# CM4_IO_Conn.net
KiCad netlist of a schematic drawn in Altium Designer
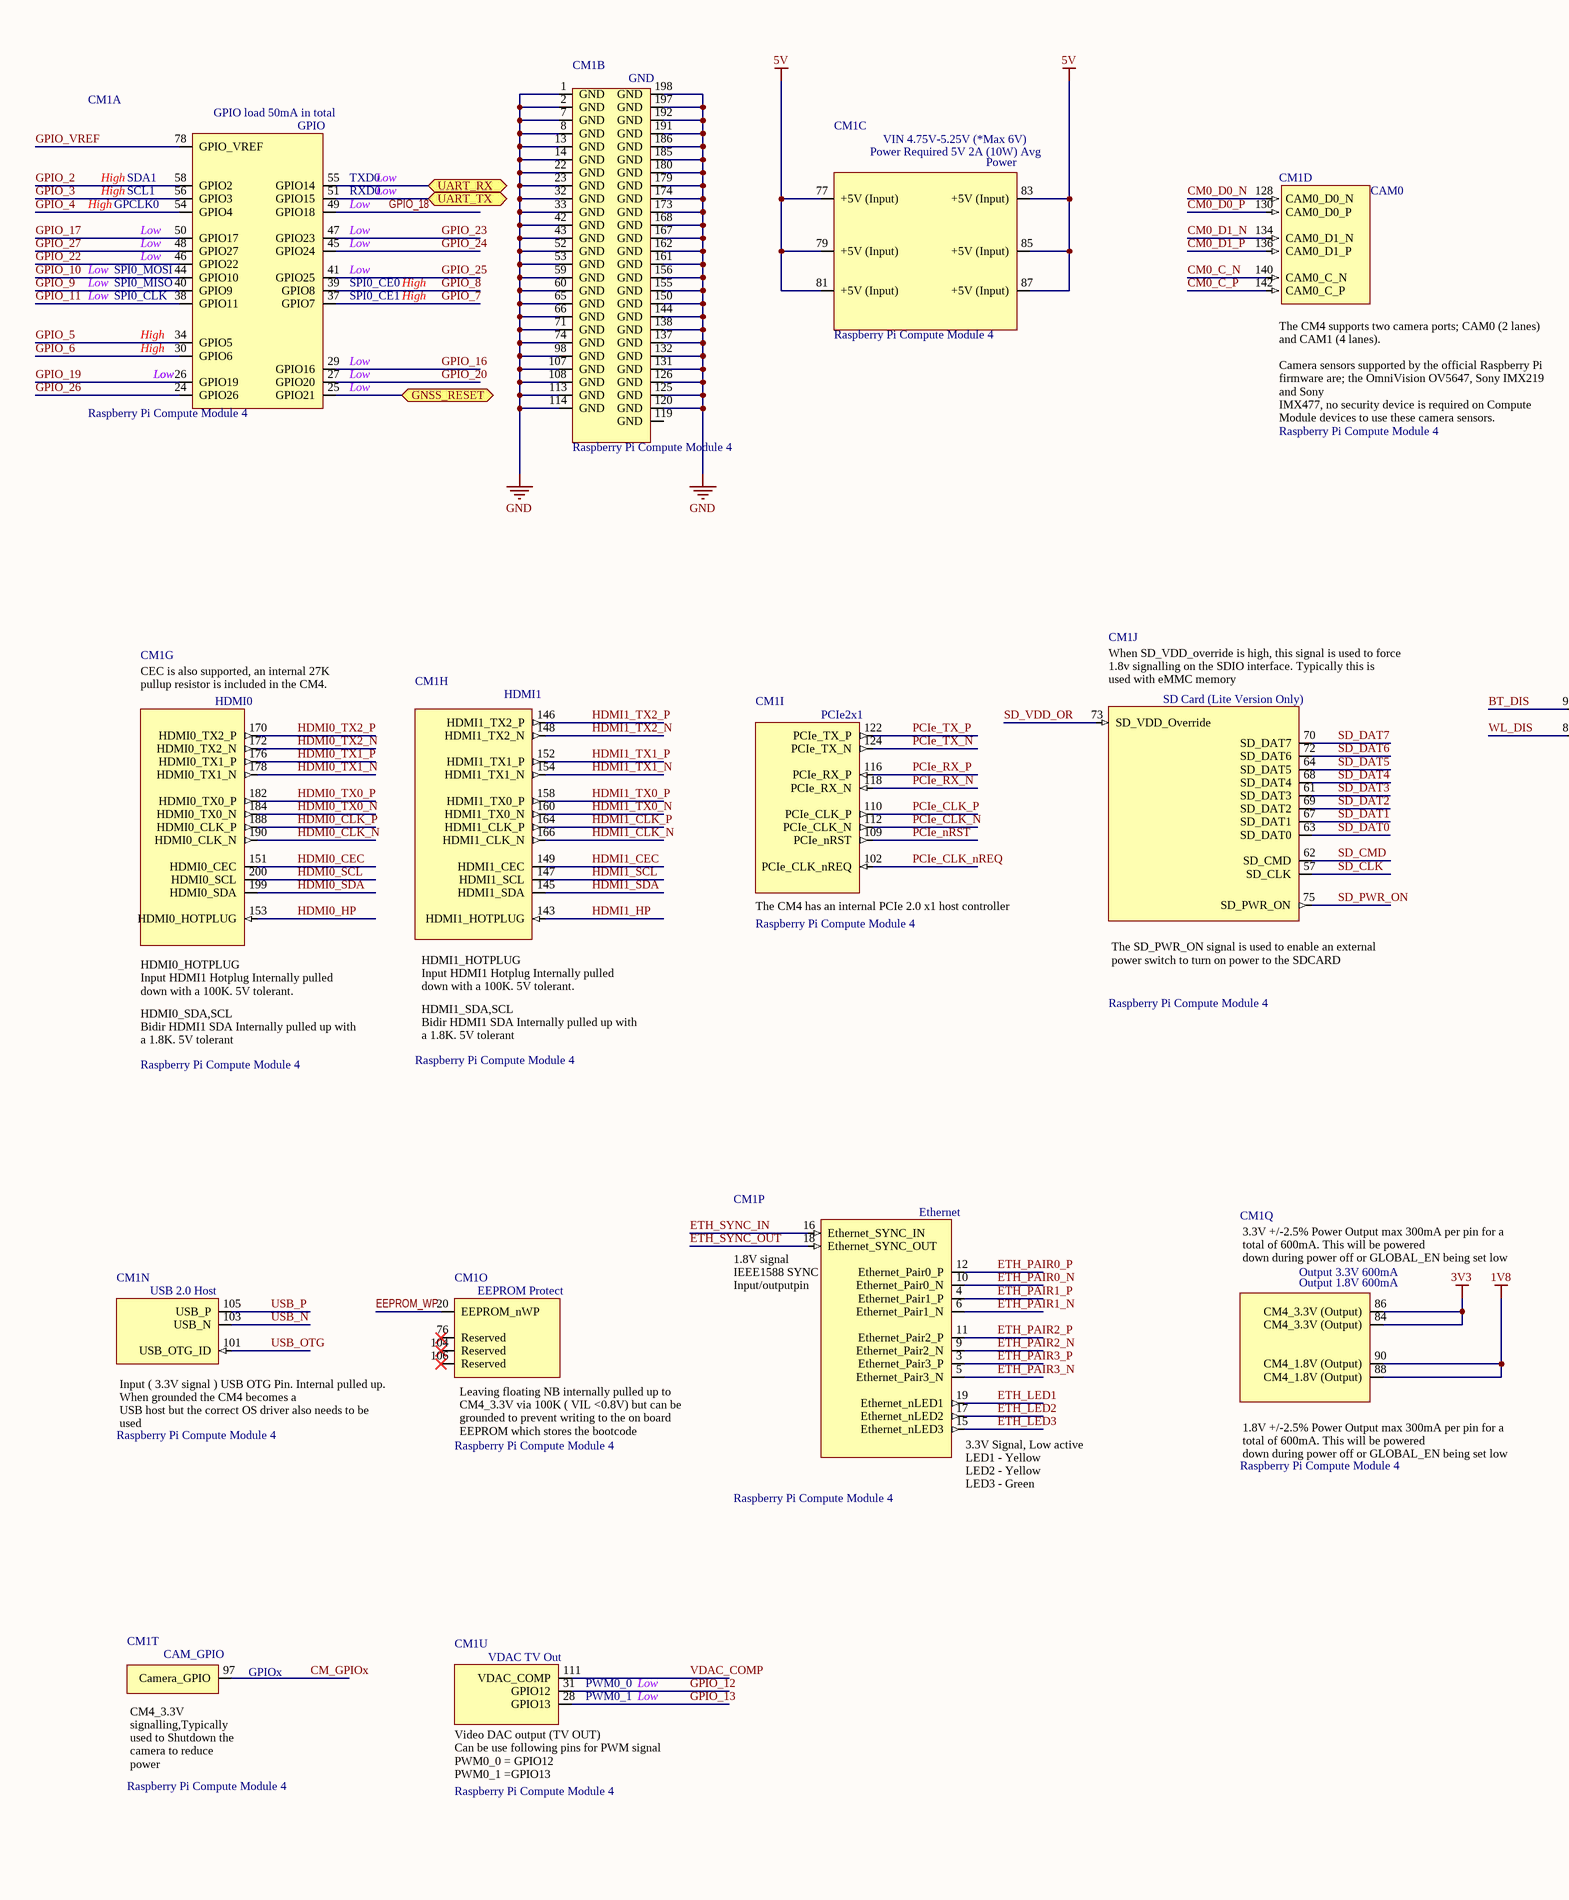
[diagram p0: CM4_IO_Conn.SchDoc, left]
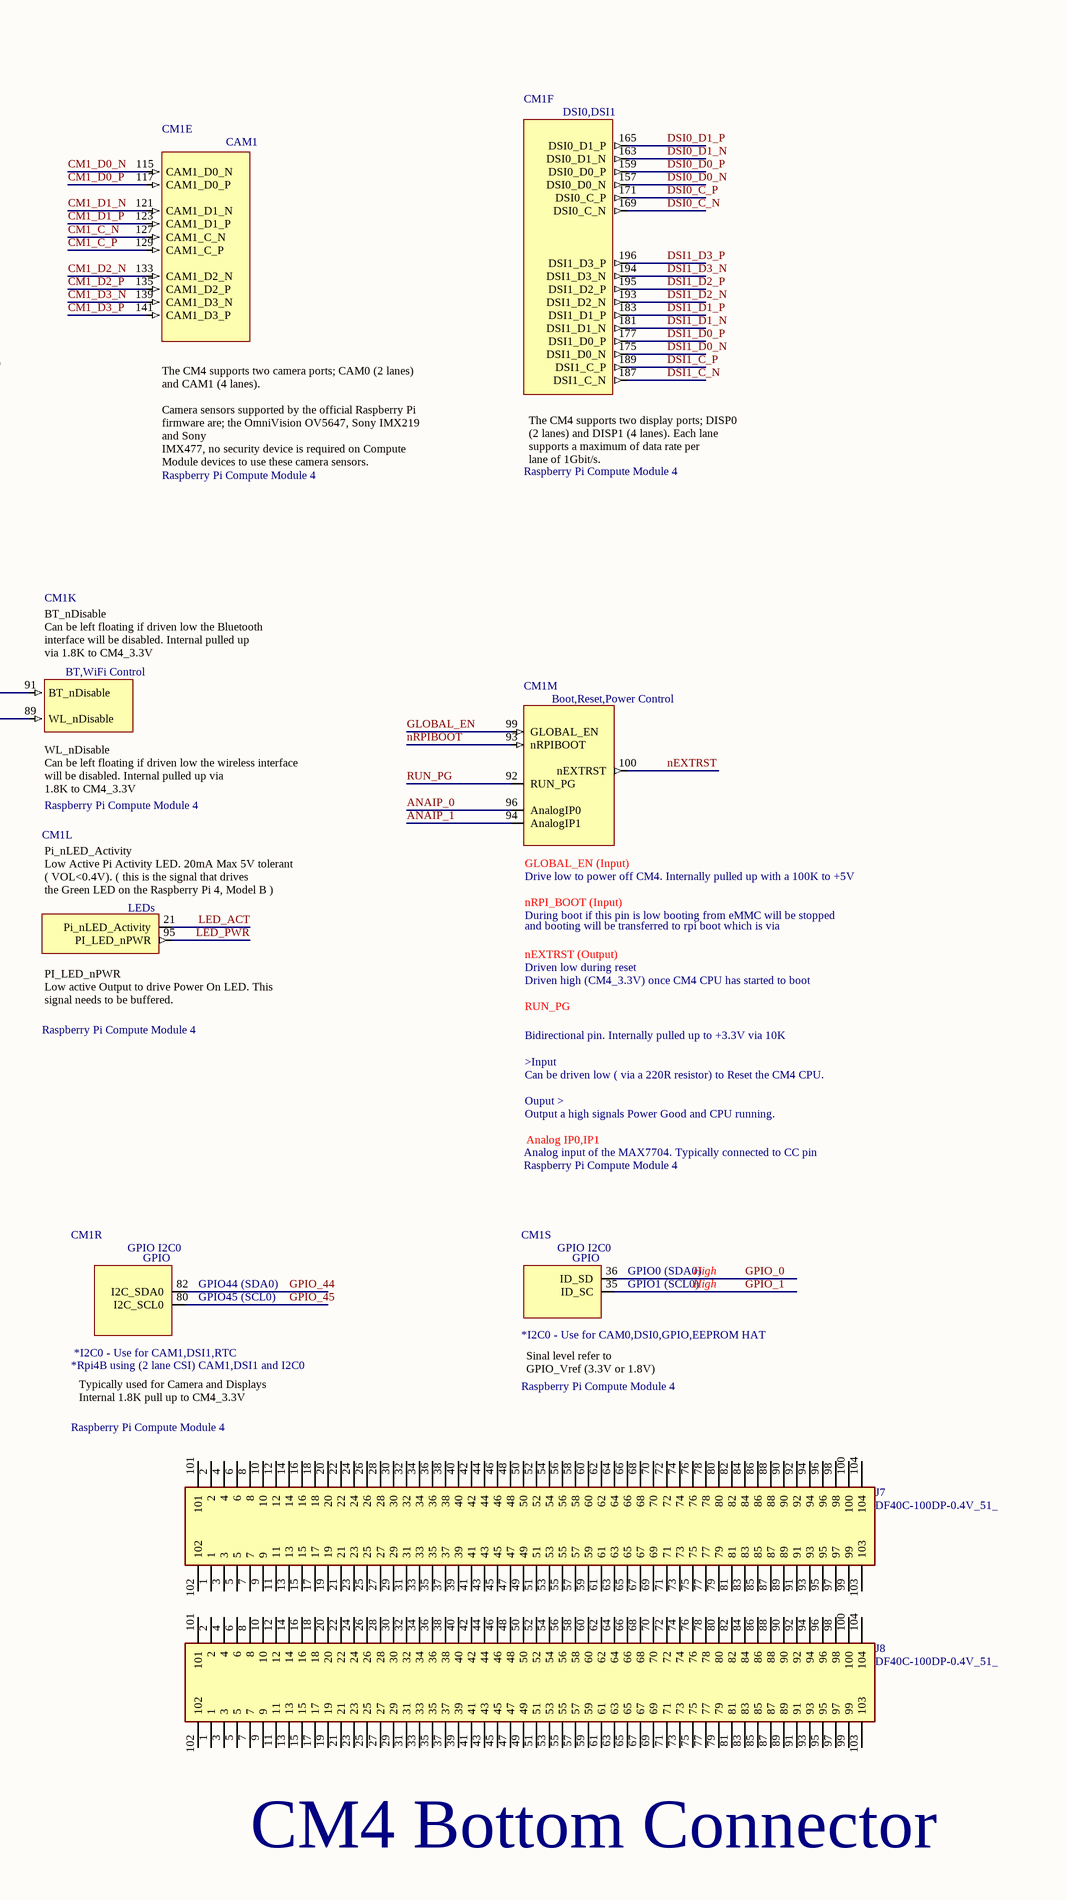
[diagram p1: CM4_IO_Conn.SchDoc, right]

(export (version "E")
  (design (tool "Eeschema 10.0.6"))
  (components
    (comp (ref "CM1")
      (value "Raspberry Pi Compute Module 4")
      (footprint "CM4-DF40HC(3.0)-100DS-0.4v_3mm_1.5mm")
      (description "Raspberry Pi Compute Module 4 by Amornthep Phunsin")
      (libsource (lib "CM4") (part "CM4"))
    )
    (comp (ref "J7")
      (value "DF40C-100DP-0.4V_51_")
      (footprint "SamacSys:DF40C100DP04V51")
      (description "Connector")
      (fields
        (field (name "MANUFACTURER_PART_NUMBER") "DF40C-100DP-0.4V(51)")
        (field (name "MOUSER PART NUMBER") "798-DF40C100DP0.4V51")
      )
      (libsource (lib "SamacSys") (part "DF40C-100DP-0.4V_51_"))
    )
    (comp (ref "J8")
      (value "DF40C-100DP-0.4V_51_")
      (footprint "SamacSys:DF40C100DP04V51")
      (description "Connector")
      (fields
        (field (name "MANUFACTURER_PART_NUMBER") "DF40C-100DP-0.4V(51)")
        (field (name "MOUSER PART NUMBER") "798-DF40C100DP0.4V51")
      )
      (libsource (lib "SamacSys") (part "DF40C-100DP-0.4V_51_"))
    )
  )
  (nets
    (net (code "1") (name "/ANAIP_0") (class "Default")
      (node (ref "CM1") (pin "96") (pinfunction "AnalogIP0_96") (pintype "passive"))
    )
    (net (code "2") (name "/ANAIP_1") (class "Default")
      (node (ref "CM1") (pin "94") (pinfunction "AnalogIP1_94") (pintype "passive"))
    )
    (net (code "3") (name "/BT_DIS") (class "Default")
      (node (ref "CM1") (pin "91") (pinfunction "BT_nDisable_91") (pintype "input"))
    )
    (net (code "4") (name "/CM0_C_N") (class "Default")
      (node (ref "CM1") (pin "140") (pinfunction "CAM0_C_N_140") (pintype "input"))
    )
    (net (code "5") (name "/CM0_C_P") (class "Default")
      (node (ref "CM1") (pin "142") (pinfunction "CAM0_C_P_142") (pintype "input"))
    )
    (net (code "6") (name "/CM0_D0_N") (class "Default")
      (node (ref "CM1") (pin "128") (pinfunction "CAM0_D0_N_128") (pintype "input"))
    )
    (net (code "7") (name "/CM0_D0_P") (class "Default")
      (node (ref "CM1") (pin "130") (pinfunction "CAM0_D0_P_130") (pintype "input"))
    )
    (net (code "8") (name "/CM0_D1_N") (class "Default")
      (node (ref "CM1") (pin "134") (pinfunction "CAM0_D1_N_134") (pintype "input"))
    )
    (net (code "9") (name "/CM0_D1_P") (class "Default")
      (node (ref "CM1") (pin "136") (pinfunction "CAM0_D1_P_136") (pintype "input"))
    )
    (net (code "10") (name "/CM1_C_N") (class "Default")
      (node (ref "CM1") (pin "127") (pinfunction "CAM1_C_N_127") (pintype "input"))
    )
    (net (code "11") (name "/CM1_C_P") (class "Default")
      (node (ref "CM1") (pin "129") (pinfunction "CAM1_C_P_129") (pintype "input"))
    )
    (net (code "12") (name "/CM1_D0_N") (class "Default")
      (node (ref "CM1") (pin "115") (pinfunction "CAM1_D0_N_115") (pintype "input"))
    )
    (net (code "13") (name "/CM1_D0_P") (class "Default")
      (node (ref "CM1") (pin "117") (pinfunction "CAM1_D0_P_117") (pintype "input"))
    )
    (net (code "14") (name "/CM1_D1_N") (class "Default")
      (node (ref "CM1") (pin "121") (pinfunction "CAM1_D1_N_121") (pintype "input"))
    )
    (net (code "15") (name "/CM1_D1_P") (class "Default")
      (node (ref "CM1") (pin "123") (pinfunction "CAM1_D1_P_123") (pintype "input"))
    )
    (net (code "16") (name "/CM1_D2_N") (class "Default")
      (node (ref "CM1") (pin "133") (pinfunction "CAM1_D2_N_133") (pintype "input"))
    )
    (net (code "17") (name "/CM1_D2_P") (class "Default")
      (node (ref "CM1") (pin "135") (pinfunction "CAM1_D2_P_135") (pintype "input"))
    )
    (net (code "18") (name "/CM1_D3_N") (class "Default")
      (node (ref "CM1") (pin "139") (pinfunction "CAM1_D3_N_139") (pintype "input"))
    )
    (net (code "19") (name "/CM1_D3_P") (class "Default")
      (node (ref "CM1") (pin "141") (pinfunction "CAM1_D3_P_141") (pintype "input"))
    )
    (net (code "20") (name "/CM_GPIOx") (class "Default")
      (node (ref "CM1") (pin "97") (pinfunction "Camera_GPIO_97") (pintype "passive"))
    )
    (net (code "21") (name "/DSI0_C_N") (class "Default")
      (node (ref "CM1") (pin "169") (pinfunction "DSI0_C_N_169") (pintype "output"))
    )
    (net (code "22") (name "/DSI0_C_P") (class "Default")
      (node (ref "CM1") (pin "171") (pinfunction "DSI0_C_P_171") (pintype "output"))
    )
    (net (code "23") (name "/DSI0_D0_N") (class "Default")
      (node (ref "CM1") (pin "157") (pinfunction "DSI0_D0_N_157") (pintype "output"))
    )
    (net (code "24") (name "/DSI0_D0_P") (class "Default")
      (node (ref "CM1") (pin "159") (pinfunction "DSI0_D0_P_159") (pintype "output"))
    )
    (net (code "25") (name "/DSI0_D1_N") (class "Default")
      (node (ref "CM1") (pin "163") (pinfunction "DSI0_D1_N_163") (pintype "output"))
    )
    (net (code "26") (name "/DSI0_D1_P") (class "Default")
      (node (ref "CM1") (pin "165") (pinfunction "DSI0_D1_P_165") (pintype "output"))
    )
    (net (code "27") (name "/DSI1_C_N") (class "Default")
      (node (ref "CM1") (pin "187") (pinfunction "DSI1_C_N_187") (pintype "output"))
    )
    (net (code "28") (name "/DSI1_C_P") (class "Default")
      (node (ref "CM1") (pin "189") (pinfunction "DSI1_C_P_189") (pintype "output"))
    )
    (net (code "29") (name "/DSI1_D0_N") (class "Default")
      (node (ref "CM1") (pin "175") (pinfunction "DSI1_D0_N_175") (pintype "output"))
    )
    (net (code "30") (name "/DSI1_D0_P") (class "Default")
      (node (ref "CM1") (pin "177") (pinfunction "DSI1_D0_P_177") (pintype "output"))
    )
    (net (code "31") (name "/DSI1_D1_N") (class "Default")
      (node (ref "CM1") (pin "181") (pinfunction "DSI1_D1_N_181") (pintype "output"))
    )
    (net (code "32") (name "/DSI1_D1_P") (class "Default")
      (node (ref "CM1") (pin "183") (pinfunction "DSI1_D1_P_183") (pintype "output"))
    )
    (net (code "33") (name "/DSI1_D2_N") (class "Default")
      (node (ref "CM1") (pin "193") (pinfunction "DSI1_D2_N_193") (pintype "output"))
    )
    (net (code "34") (name "/DSI1_D2_P") (class "Default")
      (node (ref "CM1") (pin "195") (pinfunction "DSI1_D2_P_195") (pintype "output"))
    )
    (net (code "35") (name "/DSI1_D3_N") (class "Default")
      (node (ref "CM1") (pin "194") (pinfunction "DSI1_D3_N_194") (pintype "output"))
    )
    (net (code "36") (name "/DSI1_D3_P") (class "Default")
      (node (ref "CM1") (pin "196") (pinfunction "DSI1_D3_P_196") (pintype "output"))
    )
    (net (code "37") (name "/EEPROM_WP") (class "Default")
      (node (ref "CM1") (pin "20") (pinfunction "EEPROM_nWP_20") (pintype "passive"))
    )
    (net (code "38") (name "/ETH_LED1") (class "Default")
      (node (ref "CM1") (pin "19") (pinfunction "Ethernet_nLED1_19") (pintype "output"))
    )
    (net (code "39") (name "/ETH_LED2") (class "Default")
      (node (ref "CM1") (pin "17") (pinfunction "Ethernet_nLED2_17") (pintype "output"))
    )
    (net (code "40") (name "/ETH_LED3") (class "Default")
      (node (ref "CM1") (pin "15") (pinfunction "Ethernet_nLED3_15") (pintype "output"))
    )
    (net (code "41") (name "/ETH_PAIR0_N") (class "Default")
      (node (ref "CM1") (pin "10") (pinfunction "Ethernet_Pair0_N_10") (pintype "passive"))
    )
    (net (code "42") (name "/ETH_PAIR0_P") (class "Default")
      (node (ref "CM1") (pin "12") (pinfunction "Ethernet_Pair0_P_12") (pintype "passive"))
    )
    (net (code "43") (name "/ETH_PAIR1_N") (class "Default")
      (node (ref "CM1") (pin "6") (pinfunction "Ethernet_Pair1_N_6") (pintype "passive"))
    )
    (net (code "44") (name "/ETH_PAIR1_P") (class "Default")
      (node (ref "CM1") (pin "4") (pinfunction "Ethernet_Pair1_P_4") (pintype "passive"))
    )
    (net (code "45") (name "/ETH_PAIR2_N") (class "Default")
      (node (ref "CM1") (pin "9") (pinfunction "Ethernet_Pair2_N_9") (pintype "passive"))
    )
    (net (code "46") (name "/ETH_PAIR2_P") (class "Default")
      (node (ref "CM1") (pin "11") (pinfunction "Ethernet_Pair2_P_11") (pintype "passive"))
    )
    (net (code "47") (name "/ETH_PAIR3_N") (class "Default")
      (node (ref "CM1") (pin "5") (pinfunction "Ethernet_Pair3_N_5") (pintype "passive"))
    )
    (net (code "48") (name "/ETH_PAIR3_P") (class "Default")
      (node (ref "CM1") (pin "3") (pinfunction "Ethernet_Pair3_P_3") (pintype "passive"))
    )
    (net (code "49") (name "/ETH_SYNC_IN") (class "Default")
      (node (ref "CM1") (pin "16") (pinfunction "Ethernet_SYNC_IN_16") (pintype "input"))
    )
    (net (code "50") (name "/ETH_SYNC_OUT") (class "Default")
      (node (ref "CM1") (pin "18") (pinfunction "Ethernet_SYNC_OUT_18") (pintype "input"))
    )
    (net (code "51") (name "/GLOBAL_EN") (class "Default")
      (node (ref "CM1") (pin "99") (pinfunction "GLOBAL_EN_99") (pintype "input"))
    )
    (net (code "52") (name "/GNSS_RESET") (class "Default")
      (node (ref "CM1") (pin "25") (pinfunction "GPIO21_25") (pintype "passive"))
    )
    (net (code "53") (name "/GPIO_0") (class "Default")
      (node (ref "CM1") (pin "36") (pinfunction "ID_SD_36") (pintype "passive"))
    )
    (net (code "54") (name "/GPIO_1") (class "Default")
      (node (ref "CM1") (pin "35") (pinfunction "ID_SC_35") (pintype "passive"))
    )
    (net (code "55") (name "/GPIO_2") (class "Default")
      (node (ref "CM1") (pin "58") (pinfunction "GPIO2_58") (pintype "passive"))
    )
    (net (code "56") (name "/GPIO_3") (class "Default")
      (node (ref "CM1") (pin "56") (pinfunction "GPIO3_56") (pintype "passive"))
    )
    (net (code "57") (name "/GPIO_4") (class "Default")
      (node (ref "CM1") (pin "54") (pinfunction "GPIO4_54") (pintype "passive"))
    )
    (net (code "58") (name "/GPIO_5") (class "Default")
      (node (ref "CM1") (pin "34") (pinfunction "GPIO5_34") (pintype "passive"))
    )
    (net (code "59") (name "/GPIO_6") (class "Default")
      (node (ref "CM1") (pin "30") (pinfunction "GPIO6_30") (pintype "passive"))
    )
    (net (code "60") (name "/GPIO_7") (class "Default")
      (node (ref "CM1") (pin "37") (pinfunction "GPIO7_37") (pintype "passive"))
    )
    (net (code "61") (name "/GPIO_8") (class "Default")
      (node (ref "CM1") (pin "39") (pinfunction "GPIO8_39") (pintype "passive"))
    )
    (net (code "62") (name "/GPIO_9") (class "Default")
      (node (ref "CM1") (pin "40") (pinfunction "GPIO9_40") (pintype "passive"))
    )
    (net (code "63") (name "/GPIO_10") (class "Default")
      (node (ref "CM1") (pin "44") (pinfunction "GPIO10_44") (pintype "passive"))
    )
    (net (code "64") (name "/GPIO_11") (class "Default")
      (node (ref "CM1") (pin "38") (pinfunction "GPIO11_38") (pintype "passive"))
    )
    (net (code "65") (name "/GPIO_12") (class "Default")
      (node (ref "CM1") (pin "31") (pinfunction "GPIO12_31") (pintype "passive"))
    )
    (net (code "66") (name "/GPIO_13") (class "Default")
      (node (ref "CM1") (pin "28") (pinfunction "GPIO13_28") (pintype "passive"))
    )
    (net (code "67") (name "/GPIO_16") (class "Default")
      (node (ref "CM1") (pin "29") (pinfunction "GPIO16_29") (pintype "passive"))
    )
    (net (code "68") (name "/GPIO_17") (class "Default")
      (node (ref "CM1") (pin "50") (pinfunction "GPIO17_50") (pintype "passive"))
    )
    (net (code "69") (name "/GPIO_18") (class "Default")
      (node (ref "CM1") (pin "49") (pinfunction "GPIO18_49") (pintype "passive"))
    )
    (net (code "70") (name "/GPIO_19") (class "Default")
      (node (ref "CM1") (pin "26") (pinfunction "GPIO19_26") (pintype "passive"))
    )
    (net (code "71") (name "/GPIO_20") (class "Default")
      (node (ref "CM1") (pin "27") (pinfunction "GPIO20_27") (pintype "passive"))
    )
    (net (code "72") (name "/GPIO_22") (class "Default")
      (node (ref "CM1") (pin "46") (pinfunction "GPIO22_46") (pintype "passive"))
    )
    (net (code "73") (name "/GPIO_23") (class "Default")
      (node (ref "CM1") (pin "47") (pinfunction "GPIO23_47") (pintype "passive"))
    )
    (net (code "74") (name "/GPIO_24") (class "Default")
      (node (ref "CM1") (pin "45") (pinfunction "GPIO24_45") (pintype "passive"))
    )
    (net (code "75") (name "/GPIO_25") (class "Default")
      (node (ref "CM1") (pin "41") (pinfunction "GPIO25_41") (pintype "passive"))
    )
    (net (code "76") (name "/GPIO_26") (class "Default")
      (node (ref "CM1") (pin "24") (pinfunction "GPIO26_24") (pintype "passive"))
    )
    (net (code "77") (name "/GPIO_27") (class "Default")
      (node (ref "CM1") (pin "48") (pinfunction "GPIO27_48") (pintype "passive"))
    )
    (net (code "78") (name "/GPIO_44") (class "Default")
      (node (ref "CM1") (pin "82") (pinfunction "I2C_SDA0_82") (pintype "passive"))
    )
    (net (code "79") (name "/GPIO_45") (class "Default")
      (node (ref "CM1") (pin "80") (pinfunction "I2C_SCL0_80") (pintype "passive"))
    )
    (net (code "80") (name "/GPIO_VREF") (class "Default")
      (node (ref "CM1") (pin "78") (pinfunction "GPIO_VREF_78") (pintype "power_in"))
    )
    (net (code "81") (name "/HDMI0_CEC") (class "Default")
      (node (ref "CM1") (pin "151") (pinfunction "HDMI0_CEC_151") (pintype "open_collector"))
    )
    (net (code "82") (name "/HDMI0_CLK_N") (class "Default")
      (node (ref "CM1") (pin "190") (pinfunction "HDMI0_CLK_N_190") (pintype "output"))
    )
    (net (code "83") (name "/HDMI0_CLK_P") (class "Default")
      (node (ref "CM1") (pin "188") (pinfunction "HDMI0_CLK_P_188") (pintype "output"))
    )
    (net (code "84") (name "/HDMI0_HP") (class "Default")
      (node (ref "CM1") (pin "153") (pinfunction "HDMI0_HOTPLUG_153") (pintype "input"))
    )
    (net (code "85") (name "/HDMI0_SCL") (class "Default")
      (node (ref "CM1") (pin "200") (pinfunction "HDMI0_SCL_200") (pintype "open_collector"))
    )
    (net (code "86") (name "/HDMI0_SDA") (class "Default")
      (node (ref "CM1") (pin "199") (pinfunction "HDMI0_SDA_199") (pintype "bidirectional"))
    )
    (net (code "87") (name "/HDMI0_TX0_N") (class "Default")
      (node (ref "CM1") (pin "184") (pinfunction "HDMI0_TX0_N_184") (pintype "output"))
    )
    (net (code "88") (name "/HDMI0_TX0_P") (class "Default")
      (node (ref "CM1") (pin "182") (pinfunction "HDMI0_TX0_P_182") (pintype "output"))
    )
    (net (code "89") (name "/HDMI0_TX1_N") (class "Default")
      (node (ref "CM1") (pin "178") (pinfunction "HDMI0_TX1_N_178") (pintype "output"))
    )
    (net (code "90") (name "/HDMI0_TX1_P") (class "Default")
      (node (ref "CM1") (pin "176") (pinfunction "HDMI0_TX1_P_176") (pintype "output"))
    )
    (net (code "91") (name "/HDMI0_TX2_N") (class "Default")
      (node (ref "CM1") (pin "172") (pinfunction "HDMI0_TX2_N_172") (pintype "output"))
    )
    (net (code "92") (name "/HDMI0_TX2_P") (class "Default")
      (node (ref "CM1") (pin "170") (pinfunction "HDMI0_TX2_P_170") (pintype "output"))
    )
    (net (code "93") (name "/HDMI1_CEC") (class "Default")
      (node (ref "CM1") (pin "149") (pinfunction "HDMI1_CEC_149") (pintype "open_collector"))
    )
    (net (code "94") (name "/HDMI1_CLK_N") (class "Default")
      (node (ref "CM1") (pin "166") (pinfunction "HDMI1_CLK_N_166") (pintype "output"))
    )
    (net (code "95") (name "/HDMI1_CLK_P") (class "Default")
      (node (ref "CM1") (pin "164") (pinfunction "HDMI1_CLK_P_164") (pintype "output"))
    )
    (net (code "96") (name "/HDMI1_HP") (class "Default")
      (node (ref "CM1") (pin "143") (pinfunction "HDMI1_HOTPLUG_143") (pintype "input"))
    )
    (net (code "97") (name "/HDMI1_SCL") (class "Default")
      (node (ref "CM1") (pin "147") (pinfunction "HDMI1_SCL_147") (pintype "open_collector"))
    )
    (net (code "98") (name "/HDMI1_SDA") (class "Default")
      (node (ref "CM1") (pin "145") (pinfunction "HDMI1_SDA_145") (pintype "bidirectional"))
    )
    (net (code "99") (name "/HDMI1_TX0_N") (class "Default")
      (node (ref "CM1") (pin "160") (pinfunction "HDMI1_TX0_N_160") (pintype "output"))
    )
    (net (code "100") (name "/HDMI1_TX0_P") (class "Default")
      (node (ref "CM1") (pin "158") (pinfunction "HDMI1_TX0_P_158") (pintype "output"))
    )
    (net (code "101") (name "/HDMI1_TX1_N") (class "Default")
      (node (ref "CM1") (pin "154") (pinfunction "HDMI1_TX1_N_154") (pintype "output"))
    )
    (net (code "102") (name "/HDMI1_TX1_P") (class "Default")
      (node (ref "CM1") (pin "152") (pinfunction "HDMI1_TX1_P_152") (pintype "output"))
    )
    (net (code "103") (name "/HDMI1_TX2_N") (class "Default")
      (node (ref "CM1") (pin "148") (pinfunction "HDMI1_TX2_N_148") (pintype "output"))
    )
    (net (code "104") (name "/HDMI1_TX2_P") (class "Default")
      (node (ref "CM1") (pin "146") (pinfunction "HDMI1_TX2_P_146") (pintype "output"))
    )
    (net (code "105") (name "/LED_ACT") (class "Default")
      (node (ref "CM1") (pin "21") (pinfunction "Pi_nLED_Activity_21") (pintype "open_collector"))
    )
    (net (code "106") (name "/LED_PWR") (class "Default")
      (node (ref "CM1") (pin "95") (pinfunction "PI_LED_nPWR_95") (pintype "output"))
    )
    (net (code "107") (name "/PCIe_CLK_N") (class "Default")
      (node (ref "CM1") (pin "112") (pinfunction "PCIe_CLK_N_112") (pintype "output"))
    )
    (net (code "108") (name "/PCIe_CLK_P") (class "Default")
      (node (ref "CM1") (pin "110") (pinfunction "PCIe_CLK_P_110") (pintype "output"))
    )
    (net (code "109") (name "/PCIe_CLK_nREQ") (class "Default")
      (node (ref "CM1") (pin "102") (pinfunction "PCIe_CLK_nREQ_102") (pintype "input"))
    )
    (net (code "110") (name "/PCIe_RX_N") (class "Default")
      (node (ref "CM1") (pin "118") (pinfunction "PCIe_RX_N_118") (pintype "input"))
    )
    (net (code "111") (name "/PCIe_RX_P") (class "Default")
      (node (ref "CM1") (pin "116") (pinfunction "PCIe_RX_P_116") (pintype "input"))
    )
    (net (code "112") (name "/PCIe_TX_N") (class "Default")
      (node (ref "CM1") (pin "124") (pinfunction "PCIe_TX_N_124") (pintype "output"))
    )
    (net (code "113") (name "/PCIe_TX_P") (class "Default")
      (node (ref "CM1") (pin "122") (pinfunction "PCIe_TX_P_122") (pintype "output"))
    )
    (net (code "114") (name "/PCIe_nRST") (class "Default")
      (node (ref "CM1") (pin "109") (pinfunction "PCIe_nRST_109") (pintype "output"))
    )
    (net (code "115") (name "/RUN_PG") (class "Default")
      (node (ref "CM1") (pin "92") (pinfunction "RUN_PG_92") (pintype "passive"))
    )
    (net (code "116") (name "/SD_CLK") (class "Default")
      (node (ref "CM1") (pin "57") (pinfunction "SD_CLK_57") (pintype "passive"))
    )
    (net (code "117") (name "/SD_CMD") (class "Default")
      (node (ref "CM1") (pin "62") (pinfunction "SD_CMD_62") (pintype "passive"))
    )
    (net (code "118") (name "/SD_DAT0") (class "Default")
      (node (ref "CM1") (pin "63") (pinfunction "SD_DAT0_63") (pintype "passive"))
    )
    (net (code "119") (name "/SD_DAT1") (class "Default")
      (node (ref "CM1") (pin "67") (pinfunction "SD_DAT1_67") (pintype "passive"))
    )
    (net (code "120") (name "/SD_DAT2") (class "Default")
      (node (ref "CM1") (pin "69") (pinfunction "SD_DAT2_69") (pintype "passive"))
    )
    (net (code "121") (name "/SD_DAT3") (class "Default")
      (node (ref "CM1") (pin "61") (pinfunction "SD_DAT3_61") (pintype "passive"))
    )
    (net (code "122") (name "/SD_DAT4") (class "Default")
      (node (ref "CM1") (pin "68") (pinfunction "SD_DAT4_68") (pintype "passive"))
    )
    (net (code "123") (name "/SD_DAT5") (class "Default")
      (node (ref "CM1") (pin "64") (pinfunction "SD_DAT5_64") (pintype "passive"))
    )
    (net (code "124") (name "/SD_DAT6") (class "Default")
      (node (ref "CM1") (pin "72") (pinfunction "SD_DAT6_72") (pintype "passive"))
    )
    (net (code "125") (name "/SD_DAT7") (class "Default")
      (node (ref "CM1") (pin "70") (pinfunction "SD_DAT7_70") (pintype "passive"))
    )
    (net (code "126") (name "/SD_PWR_ON") (class "Default")
      (node (ref "CM1") (pin "75") (pinfunction "SD_PWR_ON_75") (pintype "output"))
    )
    (net (code "127") (name "/SD_VDD_OR") (class "Default")
      (node (ref "CM1") (pin "73") (pinfunction "SD_VDD_Override_73") (pintype "input"))
    )
    (net (code "128") (name "/UART_RX") (class "Default")
      (node (ref "CM1") (pin "55") (pinfunction "GPIO14_55") (pintype "passive"))
    )
    (net (code "129") (name "/UART_TX") (class "Default")
      (node (ref "CM1") (pin "51") (pinfunction "GPIO15_51") (pintype "passive"))
    )
    (net (code "130") (name "/USB_N") (class "Default")
      (node (ref "CM1") (pin "103") (pinfunction "USB_N_103") (pintype "passive"))
    )
    (net (code "131") (name "/USB_OTG") (class "Default")
      (node (ref "CM1") (pin "101") (pinfunction "USB_OTG_ID_101") (pintype "input"))
    )
    (net (code "132") (name "/USB_P") (class "Default")
      (node (ref "CM1") (pin "105") (pinfunction "USB_P_105") (pintype "passive"))
    )
    (net (code "133") (name "/VDAC_COMP") (class "Default")
      (node (ref "CM1") (pin "111") (pinfunction "VDAC_COMP_111") (pintype "passive"))
    )
    (net (code "134") (name "/WL_DIS") (class "Default")
      (node (ref "CM1") (pin "89") (pinfunction "WL_nDisable_89") (pintype "input"))
    )
    (net (code "135") (name "/nEXTRST") (class "Default")
      (node (ref "CM1") (pin "100") (pinfunction "nEXTRST_100") (pintype "output"))
    )
    (net (code "136") (name "/nRPIBOOT") (class "Default")
      (node (ref "CM1") (pin "93") (pinfunction "nRPIBOOT_93") (pintype "input"))
    )
    (net (code "137") (name "1V8") (class "Default")
      (node (ref "CM1") (pin "88") (pinfunction "CM4_1.8V_(Output)_88") (pintype "power_in"))
      (node (ref "CM1") (pin "90") (pinfunction "CM4_1.8V_(Output)_90") (pintype "power_in"))
    )
    (net (code "138") (name "3V3") (class "Default")
      (node (ref "CM1") (pin "84") (pinfunction "CM4_3.3V_(Output)_84") (pintype "power_in"))
      (node (ref "CM1") (pin "86") (pinfunction "CM4_3.3V_(Output)_86") (pintype "power_in"))
    )
    (net (code "139") (name "5V") (class "Default")
      (node (ref "CM1") (pin "77") (pinfunction "+5V_(Input)_77") (pintype "power_in"))
      (node (ref "CM1") (pin "79") (pinfunction "+5V_(Input)_79") (pintype "power_in"))
      (node (ref "CM1") (pin "81") (pinfunction "+5V_(Input)_81") (pintype "power_in"))
      (node (ref "CM1") (pin "83") (pinfunction "+5V_(Input)_83") (pintype "power_in"))
      (node (ref "CM1") (pin "85") (pinfunction "+5V_(Input)_85") (pintype "power_in"))
      (node (ref "CM1") (pin "87") (pinfunction "+5V_(Input)_87") (pintype "power_in"))
    )
    (net (code "140") (name "GND") (class "Default")
      (node (ref "CM1") (pin "1") (pinfunction "GND_1") (pintype "power_in"))
      (node (ref "CM1") (pin "107") (pinfunction "GND_107") (pintype "power_in"))
      (node (ref "CM1") (pin "108") (pinfunction "GND_108") (pintype "power_in"))
      (node (ref "CM1") (pin "113") (pinfunction "GND_113") (pintype "power_in"))
      (node (ref "CM1") (pin "114") (pinfunction "GND_114") (pintype "power_in"))
      (node (ref "CM1") (pin "120") (pinfunction "GND_120") (pintype "power_in"))
      (node (ref "CM1") (pin "125") (pinfunction "GND_125") (pintype "power_in"))
      (node (ref "CM1") (pin "126") (pinfunction "GND_126") (pintype "power_in"))
      (node (ref "CM1") (pin "13") (pinfunction "GND_13") (pintype "power_in"))
      (node (ref "CM1") (pin "131") (pinfunction "GND_131") (pintype "power_in"))
      (node (ref "CM1") (pin "132") (pinfunction "GND_132") (pintype "power_in"))
      (node (ref "CM1") (pin "137") (pinfunction "GND_137") (pintype "power_in"))
      (node (ref "CM1") (pin "138") (pinfunction "GND_138") (pintype "power_in"))
      (node (ref "CM1") (pin "14") (pinfunction "GND_14") (pintype "power_in"))
      (node (ref "CM1") (pin "144") (pinfunction "GND_144") (pintype "power_in"))
      (node (ref "CM1") (pin "150") (pinfunction "GND_150") (pintype "power_in"))
      (node (ref "CM1") (pin "155") (pinfunction "GND_155") (pintype "power_in"))
      (node (ref "CM1") (pin "156") (pinfunction "GND_156") (pintype "power_in"))
      (node (ref "CM1") (pin "161") (pinfunction "GND_161") (pintype "power_in"))
      (node (ref "CM1") (pin "162") (pinfunction "GND_162") (pintype "power_in"))
      (node (ref "CM1") (pin "167") (pinfunction "GND_167") (pintype "power_in"))
      (node (ref "CM1") (pin "168") (pinfunction "GND_168") (pintype "power_in"))
      (node (ref "CM1") (pin "173") (pinfunction "GND_173") (pintype "power_in"))
      (node (ref "CM1") (pin "174") (pinfunction "GND_174") (pintype "power_in"))
      (node (ref "CM1") (pin "179") (pinfunction "GND_179") (pintype "power_in"))
      (node (ref "CM1") (pin "180") (pinfunction "GND_180") (pintype "power_in"))
      (node (ref "CM1") (pin "185") (pinfunction "GND_185") (pintype "power_in"))
      (node (ref "CM1") (pin "186") (pinfunction "GND_186") (pintype "power_in"))
      (node (ref "CM1") (pin "191") (pinfunction "GND_191") (pintype "power_in"))
      (node (ref "CM1") (pin "192") (pinfunction "GND_192") (pintype "power_in"))
      (node (ref "CM1") (pin "197") (pinfunction "GND_197") (pintype "power_in"))
      (node (ref "CM1") (pin "198") (pinfunction "GND_198") (pintype "power_in"))
      (node (ref "CM1") (pin "2") (pinfunction "GND_2") (pintype "power_in"))
      (node (ref "CM1") (pin "22") (pinfunction "GND_22") (pintype "power_in"))
      (node (ref "CM1") (pin "23") (pinfunction "GND_23") (pintype "power_in"))
      (node (ref "CM1") (pin "32") (pinfunction "GND_32") (pintype "power_in"))
      (node (ref "CM1") (pin "33") (pinfunction "GND_33") (pintype "power_in"))
      (node (ref "CM1") (pin "42") (pinfunction "GND_42") (pintype "power_in"))
      (node (ref "CM1") (pin "43") (pinfunction "GND_43") (pintype "power_in"))
      (node (ref "CM1") (pin "52") (pinfunction "GND_52") (pintype "power_in"))
      (node (ref "CM1") (pin "53") (pinfunction "GND_53") (pintype "power_in"))
      (node (ref "CM1") (pin "59") (pinfunction "GND_59") (pintype "power_in"))
      (node (ref "CM1") (pin "60") (pinfunction "GND_60") (pintype "power_in"))
      (node (ref "CM1") (pin "65") (pinfunction "GND_65") (pintype "power_in"))
      (node (ref "CM1") (pin "66") (pinfunction "GND_66") (pintype "power_in"))
      (node (ref "CM1") (pin "7") (pinfunction "GND_7") (pintype "power_in"))
      (node (ref "CM1") (pin "71") (pinfunction "GND_71") (pintype "power_in"))
      (node (ref "CM1") (pin "74") (pinfunction "GND_74") (pintype "power_in"))
      (node (ref "CM1") (pin "8") (pinfunction "GND_8") (pintype "power_in"))
      (node (ref "CM1") (pin "98") (pinfunction "GND_98") (pintype "power_in"))
    )
    (net (code "141") (name "unconnected-(CM1B-GND-Pad119)") (class "Default")
      (node (ref "CM1") (pin "119") (pinfunction "GND_119") (pintype "power_in"))
    )
    (net (code "142") (name "unconnected-(CM1O-Reserved-Pad76)") (class "Default")
      (node (ref "CM1") (pin "76") (pinfunction "Reserved_76") (pintype "passive+no_connect"))
    )
    (net (code "143") (name "unconnected-(CM1O-Reserved-Pad104)") (class "Default")
      (node (ref "CM1") (pin "104") (pinfunction "Reserved_104") (pintype "passive+no_connect"))
    )
    (net (code "144") (name "unconnected-(CM1O-Reserved-Pad106)") (class "Default")
      (node (ref "CM1") (pin "106") (pinfunction "Reserved_106") (pintype "passive+no_connect"))
    )
    (net (code "145") (name "unconnected-(J7-Pad1)") (class "Default")
      (node (ref "J7") (pin "1") (pinfunction "1_1") (pintype "passive"))
    )
    (net (code "146") (name "unconnected-(J7-Pad2)") (class "Default")
      (node (ref "J7") (pin "2") (pinfunction "2_2") (pintype "passive"))
    )
    (net (code "147") (name "unconnected-(J7-Pad3)") (class "Default")
      (node (ref "J7") (pin "3") (pinfunction "3_3") (pintype "passive"))
    )
    (net (code "148") (name "unconnected-(J7-Pad4)") (class "Default")
      (node (ref "J7") (pin "4") (pinfunction "4_4") (pintype "passive"))
    )
    (net (code "149") (name "unconnected-(J7-Pad5)") (class "Default")
      (node (ref "J7") (pin "5") (pinfunction "5_5") (pintype "passive"))
    )
    (net (code "150") (name "unconnected-(J7-Pad6)") (class "Default")
      (node (ref "J7") (pin "6") (pinfunction "6_6") (pintype "passive"))
    )
    (net (code "151") (name "unconnected-(J7-Pad7)") (class "Default")
      (node (ref "J7") (pin "7") (pinfunction "7_7") (pintype "passive"))
    )
    (net (code "152") (name "unconnected-(J7-Pad8)") (class "Default")
      (node (ref "J7") (pin "8") (pinfunction "8_8") (pintype "passive"))
    )
    (net (code "153") (name "unconnected-(J7-Pad9)") (class "Default")
      (node (ref "J7") (pin "9") (pinfunction "9_9") (pintype "passive"))
    )
    (net (code "154") (name "unconnected-(J7-Pad10)") (class "Default")
      (node (ref "J7") (pin "10") (pinfunction "10_10") (pintype "passive"))
    )
    (net (code "155") (name "unconnected-(J7-Pad11)") (class "Default")
      (node (ref "J7") (pin "11") (pinfunction "11_11") (pintype "passive"))
    )
    (net (code "156") (name "unconnected-(J7-Pad12)") (class "Default")
      (node (ref "J7") (pin "12") (pinfunction "12_12") (pintype "passive"))
    )
    (net (code "157") (name "unconnected-(J7-Pad13)") (class "Default")
      (node (ref "J7") (pin "13") (pinfunction "13_13") (pintype "passive"))
    )
    (net (code "158") (name "unconnected-(J7-Pad14)") (class "Default")
      (node (ref "J7") (pin "14") (pinfunction "14_14") (pintype "passive"))
    )
    (net (code "159") (name "unconnected-(J7-Pad15)") (class "Default")
      (node (ref "J7") (pin "15") (pinfunction "15_15") (pintype "passive"))
    )
    (net (code "160") (name "unconnected-(J7-Pad16)") (class "Default")
      (node (ref "J7") (pin "16") (pinfunction "16_16") (pintype "passive"))
    )
    (net (code "161") (name "unconnected-(J7-Pad17)") (class "Default")
      (node (ref "J7") (pin "17") (pinfunction "17_17") (pintype "passive"))
    )
    (net (code "162") (name "unconnected-(J7-Pad18)") (class "Default")
      (node (ref "J7") (pin "18") (pinfunction "18_18") (pintype "passive"))
    )
    (net (code "163") (name "unconnected-(J7-Pad19)") (class "Default")
      (node (ref "J7") (pin "19") (pinfunction "19_19") (pintype "passive"))
    )
    (net (code "164") (name "unconnected-(J7-Pad20)") (class "Default")
      (node (ref "J7") (pin "20") (pinfunction "20_20") (pintype "passive"))
    )
    (net (code "165") (name "unconnected-(J7-Pad21)") (class "Default")
      (node (ref "J7") (pin "21") (pinfunction "21_21") (pintype "passive"))
    )
    (net (code "166") (name "unconnected-(J7-Pad22)") (class "Default")
      (node (ref "J7") (pin "22") (pinfunction "22_22") (pintype "passive"))
    )
    (net (code "167") (name "unconnected-(J7-Pad23)") (class "Default")
      (node (ref "J7") (pin "23") (pinfunction "23_23") (pintype "passive"))
    )
    (net (code "168") (name "unconnected-(J7-Pad24)") (class "Default")
      (node (ref "J7") (pin "24") (pinfunction "24_24") (pintype "passive"))
    )
    (net (code "169") (name "unconnected-(J7-Pad25)") (class "Default")
      (node (ref "J7") (pin "25") (pinfunction "25_25") (pintype "passive"))
    )
    (net (code "170") (name "unconnected-(J7-Pad26)") (class "Default")
      (node (ref "J7") (pin "26") (pinfunction "26_26") (pintype "passive"))
    )
    (net (code "171") (name "unconnected-(J7-Pad27)") (class "Default")
      (node (ref "J7") (pin "27") (pinfunction "27_27") (pintype "passive"))
    )
    (net (code "172") (name "unconnected-(J7-Pad28)") (class "Default")
      (node (ref "J7") (pin "28") (pinfunction "28_28") (pintype "passive"))
    )
    (net (code "173") (name "unconnected-(J7-Pad29)") (class "Default")
      (node (ref "J7") (pin "29") (pinfunction "29_29") (pintype "passive"))
    )
    (net (code "174") (name "unconnected-(J7-Pad30)") (class "Default")
      (node (ref "J7") (pin "30") (pinfunction "30_30") (pintype "passive"))
    )
    (net (code "175") (name "unconnected-(J7-Pad31)") (class "Default")
      (node (ref "J7") (pin "31") (pinfunction "31_31") (pintype "passive"))
    )
    (net (code "176") (name "unconnected-(J7-Pad32)") (class "Default")
      (node (ref "J7") (pin "32") (pinfunction "32_32") (pintype "passive"))
    )
    (net (code "177") (name "unconnected-(J7-Pad33)") (class "Default")
      (node (ref "J7") (pin "33") (pinfunction "33_33") (pintype "passive"))
    )
    (net (code "178") (name "unconnected-(J7-Pad34)") (class "Default")
      (node (ref "J7") (pin "34") (pinfunction "34_34") (pintype "passive"))
    )
    (net (code "179") (name "unconnected-(J7-Pad35)") (class "Default")
      (node (ref "J7") (pin "35") (pinfunction "35_35") (pintype "passive"))
    )
    (net (code "180") (name "unconnected-(J7-Pad36)") (class "Default")
      (node (ref "J7") (pin "36") (pinfunction "36_36") (pintype "passive"))
    )
    (net (code "181") (name "unconnected-(J7-Pad37)") (class "Default")
      (node (ref "J7") (pin "37") (pinfunction "37_37") (pintype "passive"))
    )
    (net (code "182") (name "unconnected-(J7-Pad38)") (class "Default")
      (node (ref "J7") (pin "38") (pinfunction "38_38") (pintype "passive"))
    )
    (net (code "183") (name "unconnected-(J7-Pad39)") (class "Default")
      (node (ref "J7") (pin "39") (pinfunction "39_39") (pintype "passive"))
    )
    (net (code "184") (name "unconnected-(J7-Pad40)") (class "Default")
      (node (ref "J7") (pin "40") (pinfunction "40_40") (pintype "passive"))
    )
    (net (code "185") (name "unconnected-(J7-Pad41)") (class "Default")
      (node (ref "J7") (pin "41") (pinfunction "41_41") (pintype "passive"))
    )
    (net (code "186") (name "unconnected-(J7-Pad42)") (class "Default")
      (node (ref "J7") (pin "42") (pinfunction "42_42") (pintype "passive"))
    )
    (net (code "187") (name "unconnected-(J7-Pad43)") (class "Default")
      (node (ref "J7") (pin "43") (pinfunction "43_43") (pintype "passive"))
    )
    (net (code "188") (name "unconnected-(J7-Pad44)") (class "Default")
      (node (ref "J7") (pin "44") (pinfunction "44_44") (pintype "passive"))
    )
    (net (code "189") (name "unconnected-(J7-Pad45)") (class "Default")
      (node (ref "J7") (pin "45") (pinfunction "45_45") (pintype "passive"))
    )
    (net (code "190") (name "unconnected-(J7-Pad46)") (class "Default")
      (node (ref "J7") (pin "46") (pinfunction "46_46") (pintype "passive"))
    )
    (net (code "191") (name "unconnected-(J7-Pad47)") (class "Default")
      (node (ref "J7") (pin "47") (pinfunction "47_47") (pintype "passive"))
    )
    (net (code "192") (name "unconnected-(J7-Pad48)") (class "Default")
      (node (ref "J7") (pin "48") (pinfunction "48_48") (pintype "passive"))
    )
    (net (code "193") (name "unconnected-(J7-Pad49)") (class "Default")
      (node (ref "J7") (pin "49") (pinfunction "49_49") (pintype "passive"))
    )
    (net (code "194") (name "unconnected-(J7-Pad50)") (class "Default")
      (node (ref "J7") (pin "50") (pinfunction "50_50") (pintype "passive"))
    )
    (net (code "195") (name "unconnected-(J7-Pad51)") (class "Default")
      (node (ref "J7") (pin "51") (pinfunction "51_51") (pintype "passive"))
    )
    (net (code "196") (name "unconnected-(J7-Pad52)") (class "Default")
      (node (ref "J7") (pin "52") (pinfunction "52_52") (pintype "passive"))
    )
    (net (code "197") (name "unconnected-(J7-Pad53)") (class "Default")
      (node (ref "J7") (pin "53") (pinfunction "53_53") (pintype "passive"))
    )
    (net (code "198") (name "unconnected-(J7-Pad54)") (class "Default")
      (node (ref "J7") (pin "54") (pinfunction "54_54") (pintype "passive"))
    )
    (net (code "199") (name "unconnected-(J7-Pad55)") (class "Default")
      (node (ref "J7") (pin "55") (pinfunction "55_55") (pintype "passive"))
    )
    (net (code "200") (name "unconnected-(J7-Pad56)") (class "Default")
      (node (ref "J7") (pin "56") (pinfunction "56_56") (pintype "passive"))
    )
    (net (code "201") (name "unconnected-(J7-Pad57)") (class "Default")
      (node (ref "J7") (pin "57") (pinfunction "57_57") (pintype "passive"))
    )
    (net (code "202") (name "unconnected-(J7-Pad58)") (class "Default")
      (node (ref "J7") (pin "58") (pinfunction "58_58") (pintype "passive"))
    )
    (net (code "203") (name "unconnected-(J7-Pad59)") (class "Default")
      (node (ref "J7") (pin "59") (pinfunction "59_59") (pintype "passive"))
    )
    (net (code "204") (name "unconnected-(J7-Pad60)") (class "Default")
      (node (ref "J7") (pin "60") (pinfunction "60_60") (pintype "passive"))
    )
    (net (code "205") (name "unconnected-(J7-Pad61)") (class "Default")
      (node (ref "J7") (pin "61") (pinfunction "61_61") (pintype "passive"))
    )
    (net (code "206") (name "unconnected-(J7-Pad62)") (class "Default")
      (node (ref "J7") (pin "62") (pinfunction "62_62") (pintype "passive"))
    )
    (net (code "207") (name "unconnected-(J7-Pad63)") (class "Default")
      (node (ref "J7") (pin "63") (pinfunction "63_63") (pintype "passive"))
    )
    (net (code "208") (name "unconnected-(J7-Pad64)") (class "Default")
      (node (ref "J7") (pin "64") (pinfunction "64_64") (pintype "passive"))
    )
    (net (code "209") (name "unconnected-(J7-Pad65)") (class "Default")
      (node (ref "J7") (pin "65") (pinfunction "65_65") (pintype "passive"))
    )
    (net (code "210") (name "unconnected-(J7-Pad66)") (class "Default")
      (node (ref "J7") (pin "66") (pinfunction "66_66") (pintype "passive"))
    )
    (net (code "211") (name "unconnected-(J7-Pad67)") (class "Default")
      (node (ref "J7") (pin "67") (pinfunction "67_67") (pintype "passive"))
    )
    (net (code "212") (name "unconnected-(J7-Pad68)") (class "Default")
      (node (ref "J7") (pin "68") (pinfunction "68_68") (pintype "passive"))
    )
    (net (code "213") (name "unconnected-(J7-Pad69)") (class "Default")
      (node (ref "J7") (pin "69") (pinfunction "69_69") (pintype "passive"))
    )
    (net (code "214") (name "unconnected-(J7-Pad70)") (class "Default")
      (node (ref "J7") (pin "70") (pinfunction "70_70") (pintype "passive"))
    )
    (net (code "215") (name "unconnected-(J7-Pad71)") (class "Default")
      (node (ref "J7") (pin "71") (pinfunction "71_71") (pintype "passive"))
    )
    (net (code "216") (name "unconnected-(J7-Pad72)") (class "Default")
      (node (ref "J7") (pin "72") (pinfunction "72_72") (pintype "passive"))
    )
    (net (code "217") (name "unconnected-(J7-Pad73)") (class "Default")
      (node (ref "J7") (pin "73") (pinfunction "73_73") (pintype "passive"))
    )
    (net (code "218") (name "unconnected-(J7-Pad74)") (class "Default")
      (node (ref "J7") (pin "74") (pinfunction "74_74") (pintype "passive"))
    )
    (net (code "219") (name "unconnected-(J7-Pad75)") (class "Default")
      (node (ref "J7") (pin "75") (pinfunction "75_75") (pintype "passive"))
    )
    (net (code "220") (name "unconnected-(J7-Pad76)") (class "Default")
      (node (ref "J7") (pin "76") (pinfunction "76_76") (pintype "passive"))
    )
    (net (code "221") (name "unconnected-(J7-Pad77)") (class "Default")
      (node (ref "J7") (pin "77") (pinfunction "77_77") (pintype "passive"))
    )
    (net (code "222") (name "unconnected-(J7-Pad78)") (class "Default")
      (node (ref "J7") (pin "78") (pinfunction "78_78") (pintype "passive"))
    )
    (net (code "223") (name "unconnected-(J7-Pad79)") (class "Default")
      (node (ref "J7") (pin "79") (pinfunction "79_79") (pintype "passive"))
    )
    (net (code "224") (name "unconnected-(J7-Pad80)") (class "Default")
      (node (ref "J7") (pin "80") (pinfunction "80_80") (pintype "passive"))
    )
    (net (code "225") (name "unconnected-(J7-Pad81)") (class "Default")
      (node (ref "J7") (pin "81") (pinfunction "81_81") (pintype "passive"))
    )
    (net (code "226") (name "unconnected-(J7-Pad82)") (class "Default")
      (node (ref "J7") (pin "82") (pinfunction "82_82") (pintype "passive"))
    )
    (net (code "227") (name "unconnected-(J7-Pad83)") (class "Default")
      (node (ref "J7") (pin "83") (pinfunction "83_83") (pintype "passive"))
    )
    (net (code "228") (name "unconnected-(J7-Pad84)") (class "Default")
      (node (ref "J7") (pin "84") (pinfunction "84_84") (pintype "passive"))
    )
    (net (code "229") (name "unconnected-(J7-Pad85)") (class "Default")
      (node (ref "J7") (pin "85") (pinfunction "85_85") (pintype "passive"))
    )
    (net (code "230") (name "unconnected-(J7-Pad86)") (class "Default")
      (node (ref "J7") (pin "86") (pinfunction "86_86") (pintype "passive"))
    )
    (net (code "231") (name "unconnected-(J7-Pad87)") (class "Default")
      (node (ref "J7") (pin "87") (pinfunction "87_87") (pintype "passive"))
    )
    (net (code "232") (name "unconnected-(J7-Pad88)") (class "Default")
      (node (ref "J7") (pin "88") (pinfunction "88_88") (pintype "passive"))
    )
    (net (code "233") (name "unconnected-(J7-Pad89)") (class "Default")
      (node (ref "J7") (pin "89") (pinfunction "89_89") (pintype "passive"))
    )
    (net (code "234") (name "unconnected-(J7-Pad90)") (class "Default")
      (node (ref "J7") (pin "90") (pinfunction "90_90") (pintype "passive"))
    )
    (net (code "235") (name "unconnected-(J7-Pad91)") (class "Default")
      (node (ref "J7") (pin "91") (pinfunction "91_91") (pintype "passive"))
    )
    (net (code "236") (name "unconnected-(J7-Pad92)") (class "Default")
      (node (ref "J7") (pin "92") (pinfunction "92_92") (pintype "passive"))
    )
    (net (code "237") (name "unconnected-(J7-Pad93)") (class "Default")
      (node (ref "J7") (pin "93") (pinfunction "93_93") (pintype "passive"))
    )
    (net (code "238") (name "unconnected-(J7-Pad94)") (class "Default")
      (node (ref "J7") (pin "94") (pinfunction "94_94") (pintype "passive"))
    )
    (net (code "239") (name "unconnected-(J7-Pad95)") (class "Default")
      (node (ref "J7") (pin "95") (pinfunction "95_95") (pintype "passive"))
    )
    (net (code "240") (name "unconnected-(J7-Pad96)") (class "Default")
      (node (ref "J7") (pin "96") (pinfunction "96_96") (pintype "passive"))
    )
    (net (code "241") (name "unconnected-(J7-Pad97)") (class "Default")
      (node (ref "J7") (pin "97") (pinfunction "97_97") (pintype "passive"))
    )
    (net (code "242") (name "unconnected-(J7-Pad98)") (class "Default")
      (node (ref "J7") (pin "98") (pinfunction "98_98") (pintype "passive"))
    )
    (net (code "243") (name "unconnected-(J7-Pad99)") (class "Default")
      (node (ref "J7") (pin "99") (pinfunction "99_99") (pintype "passive"))
    )
    (net (code "244") (name "unconnected-(J7-Pad100)") (class "Default")
      (node (ref "J7") (pin "100") (pinfunction "100_100") (pintype "passive"))
    )
    (net (code "245") (name "unconnected-(J7-Pad101)") (class "Default")
      (node (ref "J7") (pin "101") (pinfunction "101_101") (pintype "passive"))
    )
    (net (code "246") (name "unconnected-(J7-Pad102)") (class "Default")
      (node (ref "J7") (pin "102") (pinfunction "102_102") (pintype "passive"))
    )
    (net (code "247") (name "unconnected-(J7-Pad103)") (class "Default")
      (node (ref "J7") (pin "103") (pinfunction "103_103") (pintype "passive"))
    )
    (net (code "248") (name "unconnected-(J7-Pad104)") (class "Default")
      (node (ref "J7") (pin "104") (pinfunction "104_104") (pintype "passive"))
    )
    (net (code "249") (name "unconnected-(J8-Pad1)") (class "Default")
      (node (ref "J8") (pin "1") (pinfunction "1_1") (pintype "passive"))
    )
    (net (code "250") (name "unconnected-(J8-Pad2)") (class "Default")
      (node (ref "J8") (pin "2") (pinfunction "2_2") (pintype "passive"))
    )
    (net (code "251") (name "unconnected-(J8-Pad3)") (class "Default")
      (node (ref "J8") (pin "3") (pinfunction "3_3") (pintype "passive"))
    )
    (net (code "252") (name "unconnected-(J8-Pad4)") (class "Default")
      (node (ref "J8") (pin "4") (pinfunction "4_4") (pintype "passive"))
    )
    (net (code "253") (name "unconnected-(J8-Pad5)") (class "Default")
      (node (ref "J8") (pin "5") (pinfunction "5_5") (pintype "passive"))
    )
    (net (code "254") (name "unconnected-(J8-Pad6)") (class "Default")
      (node (ref "J8") (pin "6") (pinfunction "6_6") (pintype "passive"))
    )
    (net (code "255") (name "unconnected-(J8-Pad7)") (class "Default")
      (node (ref "J8") (pin "7") (pinfunction "7_7") (pintype "passive"))
    )
    (net (code "256") (name "unconnected-(J8-Pad8)") (class "Default")
      (node (ref "J8") (pin "8") (pinfunction "8_8") (pintype "passive"))
    )
    (net (code "257") (name "unconnected-(J8-Pad9)") (class "Default")
      (node (ref "J8") (pin "9") (pinfunction "9_9") (pintype "passive"))
    )
    (net (code "258") (name "unconnected-(J8-Pad10)") (class "Default")
      (node (ref "J8") (pin "10") (pinfunction "10_10") (pintype "passive"))
    )
    (net (code "259") (name "unconnected-(J8-Pad11)") (class "Default")
      (node (ref "J8") (pin "11") (pinfunction "11_11") (pintype "passive"))
    )
    (net (code "260") (name "unconnected-(J8-Pad12)") (class "Default")
      (node (ref "J8") (pin "12") (pinfunction "12_12") (pintype "passive"))
    )
    (net (code "261") (name "unconnected-(J8-Pad13)") (class "Default")
      (node (ref "J8") (pin "13") (pinfunction "13_13") (pintype "passive"))
    )
    (net (code "262") (name "unconnected-(J8-Pad14)") (class "Default")
      (node (ref "J8") (pin "14") (pinfunction "14_14") (pintype "passive"))
    )
    (net (code "263") (name "unconnected-(J8-Pad15)") (class "Default")
      (node (ref "J8") (pin "15") (pinfunction "15_15") (pintype "passive"))
    )
    (net (code "264") (name "unconnected-(J8-Pad16)") (class "Default")
      (node (ref "J8") (pin "16") (pinfunction "16_16") (pintype "passive"))
    )
    (net (code "265") (name "unconnected-(J8-Pad17)") (class "Default")
      (node (ref "J8") (pin "17") (pinfunction "17_17") (pintype "passive"))
    )
    (net (code "266") (name "unconnected-(J8-Pad18)") (class "Default")
      (node (ref "J8") (pin "18") (pinfunction "18_18") (pintype "passive"))
    )
    (net (code "267") (name "unconnected-(J8-Pad19)") (class "Default")
      (node (ref "J8") (pin "19") (pinfunction "19_19") (pintype "passive"))
    )
    (net (code "268") (name "unconnected-(J8-Pad20)") (class "Default")
      (node (ref "J8") (pin "20") (pinfunction "20_20") (pintype "passive"))
    )
    (net (code "269") (name "unconnected-(J8-Pad21)") (class "Default")
      (node (ref "J8") (pin "21") (pinfunction "21_21") (pintype "passive"))
    )
    (net (code "270") (name "unconnected-(J8-Pad22)") (class "Default")
      (node (ref "J8") (pin "22") (pinfunction "22_22") (pintype "passive"))
    )
    (net (code "271") (name "unconnected-(J8-Pad23)") (class "Default")
      (node (ref "J8") (pin "23") (pinfunction "23_23") (pintype "passive"))
    )
    (net (code "272") (name "unconnected-(J8-Pad24)") (class "Default")
      (node (ref "J8") (pin "24") (pinfunction "24_24") (pintype "passive"))
    )
    (net (code "273") (name "unconnected-(J8-Pad25)") (class "Default")
      (node (ref "J8") (pin "25") (pinfunction "25_25") (pintype "passive"))
    )
    (net (code "274") (name "unconnected-(J8-Pad26)") (class "Default")
      (node (ref "J8") (pin "26") (pinfunction "26_26") (pintype "passive"))
    )
    (net (code "275") (name "unconnected-(J8-Pad27)") (class "Default")
      (node (ref "J8") (pin "27") (pinfunction "27_27") (pintype "passive"))
    )
    (net (code "276") (name "unconnected-(J8-Pad28)") (class "Default")
      (node (ref "J8") (pin "28") (pinfunction "28_28") (pintype "passive"))
    )
    (net (code "277") (name "unconnected-(J8-Pad29)") (class "Default")
      (node (ref "J8") (pin "29") (pinfunction "29_29") (pintype "passive"))
    )
    (net (code "278") (name "unconnected-(J8-Pad30)") (class "Default")
      (node (ref "J8") (pin "30") (pinfunction "30_30") (pintype "passive"))
    )
    (net (code "279") (name "unconnected-(J8-Pad31)") (class "Default")
      (node (ref "J8") (pin "31") (pinfunction "31_31") (pintype "passive"))
    )
    (net (code "280") (name "unconnected-(J8-Pad32)") (class "Default")
      (node (ref "J8") (pin "32") (pinfunction "32_32") (pintype "passive"))
    )
    (net (code "281") (name "unconnected-(J8-Pad33)") (class "Default")
      (node (ref "J8") (pin "33") (pinfunction "33_33") (pintype "passive"))
    )
    (net (code "282") (name "unconnected-(J8-Pad34)") (class "Default")
      (node (ref "J8") (pin "34") (pinfunction "34_34") (pintype "passive"))
    )
    (net (code "283") (name "unconnected-(J8-Pad35)") (class "Default")
      (node (ref "J8") (pin "35") (pinfunction "35_35") (pintype "passive"))
    )
    (net (code "284") (name "unconnected-(J8-Pad36)") (class "Default")
      (node (ref "J8") (pin "36") (pinfunction "36_36") (pintype "passive"))
    )
    (net (code "285") (name "unconnected-(J8-Pad37)") (class "Default")
      (node (ref "J8") (pin "37") (pinfunction "37_37") (pintype "passive"))
    )
    (net (code "286") (name "unconnected-(J8-Pad38)") (class "Default")
      (node (ref "J8") (pin "38") (pinfunction "38_38") (pintype "passive"))
    )
    (net (code "287") (name "unconnected-(J8-Pad39)") (class "Default")
      (node (ref "J8") (pin "39") (pinfunction "39_39") (pintype "passive"))
    )
    (net (code "288") (name "unconnected-(J8-Pad40)") (class "Default")
      (node (ref "J8") (pin "40") (pinfunction "40_40") (pintype "passive"))
    )
    (net (code "289") (name "unconnected-(J8-Pad41)") (class "Default")
      (node (ref "J8") (pin "41") (pinfunction "41_41") (pintype "passive"))
    )
    (net (code "290") (name "unconnected-(J8-Pad42)") (class "Default")
      (node (ref "J8") (pin "42") (pinfunction "42_42") (pintype "passive"))
    )
    (net (code "291") (name "unconnected-(J8-Pad43)") (class "Default")
      (node (ref "J8") (pin "43") (pinfunction "43_43") (pintype "passive"))
    )
    (net (code "292") (name "unconnected-(J8-Pad44)") (class "Default")
      (node (ref "J8") (pin "44") (pinfunction "44_44") (pintype "passive"))
    )
    (net (code "293") (name "unconnected-(J8-Pad45)") (class "Default")
      (node (ref "J8") (pin "45") (pinfunction "45_45") (pintype "passive"))
    )
    (net (code "294") (name "unconnected-(J8-Pad46)") (class "Default")
      (node (ref "J8") (pin "46") (pinfunction "46_46") (pintype "passive"))
    )
    (net (code "295") (name "unconnected-(J8-Pad47)") (class "Default")
      (node (ref "J8") (pin "47") (pinfunction "47_47") (pintype "passive"))
    )
    (net (code "296") (name "unconnected-(J8-Pad48)") (class "Default")
      (node (ref "J8") (pin "48") (pinfunction "48_48") (pintype "passive"))
    )
    (net (code "297") (name "unconnected-(J8-Pad49)") (class "Default")
      (node (ref "J8") (pin "49") (pinfunction "49_49") (pintype "passive"))
    )
    (net (code "298") (name "unconnected-(J8-Pad50)") (class "Default")
      (node (ref "J8") (pin "50") (pinfunction "50_50") (pintype "passive"))
    )
    (net (code "299") (name "unconnected-(J8-Pad51)") (class "Default")
      (node (ref "J8") (pin "51") (pinfunction "51_51") (pintype "passive"))
    )
    (net (code "300") (name "unconnected-(J8-Pad52)") (class "Default")
      (node (ref "J8") (pin "52") (pinfunction "52_52") (pintype "passive"))
    )
    (net (code "301") (name "unconnected-(J8-Pad53)") (class "Default")
      (node (ref "J8") (pin "53") (pinfunction "53_53") (pintype "passive"))
    )
    (net (code "302") (name "unconnected-(J8-Pad54)") (class "Default")
      (node (ref "J8") (pin "54") (pinfunction "54_54") (pintype "passive"))
    )
    (net (code "303") (name "unconnected-(J8-Pad55)") (class "Default")
      (node (ref "J8") (pin "55") (pinfunction "55_55") (pintype "passive"))
    )
    (net (code "304") (name "unconnected-(J8-Pad56)") (class "Default")
      (node (ref "J8") (pin "56") (pinfunction "56_56") (pintype "passive"))
    )
    (net (code "305") (name "unconnected-(J8-Pad57)") (class "Default")
      (node (ref "J8") (pin "57") (pinfunction "57_57") (pintype "passive"))
    )
    (net (code "306") (name "unconnected-(J8-Pad58)") (class "Default")
      (node (ref "J8") (pin "58") (pinfunction "58_58") (pintype "passive"))
    )
    (net (code "307") (name "unconnected-(J8-Pad59)") (class "Default")
      (node (ref "J8") (pin "59") (pinfunction "59_59") (pintype "passive"))
    )
    (net (code "308") (name "unconnected-(J8-Pad60)") (class "Default")
      (node (ref "J8") (pin "60") (pinfunction "60_60") (pintype "passive"))
    )
    (net (code "309") (name "unconnected-(J8-Pad61)") (class "Default")
      (node (ref "J8") (pin "61") (pinfunction "61_61") (pintype "passive"))
    )
    (net (code "310") (name "unconnected-(J8-Pad62)") (class "Default")
      (node (ref "J8") (pin "62") (pinfunction "62_62") (pintype "passive"))
    )
    (net (code "311") (name "unconnected-(J8-Pad63)") (class "Default")
      (node (ref "J8") (pin "63") (pinfunction "63_63") (pintype "passive"))
    )
    (net (code "312") (name "unconnected-(J8-Pad64)") (class "Default")
      (node (ref "J8") (pin "64") (pinfunction "64_64") (pintype "passive"))
    )
    (net (code "313") (name "unconnected-(J8-Pad65)") (class "Default")
      (node (ref "J8") (pin "65") (pinfunction "65_65") (pintype "passive"))
    )
    (net (code "314") (name "unconnected-(J8-Pad66)") (class "Default")
      (node (ref "J8") (pin "66") (pinfunction "66_66") (pintype "passive"))
    )
    (net (code "315") (name "unconnected-(J8-Pad67)") (class "Default")
      (node (ref "J8") (pin "67") (pinfunction "67_67") (pintype "passive"))
    )
    (net (code "316") (name "unconnected-(J8-Pad68)") (class "Default")
      (node (ref "J8") (pin "68") (pinfunction "68_68") (pintype "passive"))
    )
    (net (code "317") (name "unconnected-(J8-Pad69)") (class "Default")
      (node (ref "J8") (pin "69") (pinfunction "69_69") (pintype "passive"))
    )
    (net (code "318") (name "unconnected-(J8-Pad70)") (class "Default")
      (node (ref "J8") (pin "70") (pinfunction "70_70") (pintype "passive"))
    )
    (net (code "319") (name "unconnected-(J8-Pad71)") (class "Default")
      (node (ref "J8") (pin "71") (pinfunction "71_71") (pintype "passive"))
    )
    (net (code "320") (name "unconnected-(J8-Pad72)") (class "Default")
      (node (ref "J8") (pin "72") (pinfunction "72_72") (pintype "passive"))
    )
    (net (code "321") (name "unconnected-(J8-Pad73)") (class "Default")
      (node (ref "J8") (pin "73") (pinfunction "73_73") (pintype "passive"))
    )
    (net (code "322") (name "unconnected-(J8-Pad74)") (class "Default")
      (node (ref "J8") (pin "74") (pinfunction "74_74") (pintype "passive"))
    )
    (net (code "323") (name "unconnected-(J8-Pad75)") (class "Default")
      (node (ref "J8") (pin "75") (pinfunction "75_75") (pintype "passive"))
    )
    (net (code "324") (name "unconnected-(J8-Pad76)") (class "Default")
      (node (ref "J8") (pin "76") (pinfunction "76_76") (pintype "passive"))
    )
    (net (code "325") (name "unconnected-(J8-Pad77)") (class "Default")
      (node (ref "J8") (pin "77") (pinfunction "77_77") (pintype "passive"))
    )
    (net (code "326") (name "unconnected-(J8-Pad78)") (class "Default")
      (node (ref "J8") (pin "78") (pinfunction "78_78") (pintype "passive"))
    )
    (net (code "327") (name "unconnected-(J8-Pad79)") (class "Default")
      (node (ref "J8") (pin "79") (pinfunction "79_79") (pintype "passive"))
    )
    (net (code "328") (name "unconnected-(J8-Pad80)") (class "Default")
      (node (ref "J8") (pin "80") (pinfunction "80_80") (pintype "passive"))
    )
    (net (code "329") (name "unconnected-(J8-Pad81)") (class "Default")
      (node (ref "J8") (pin "81") (pinfunction "81_81") (pintype "passive"))
    )
    (net (code "330") (name "unconnected-(J8-Pad82)") (class "Default")
      (node (ref "J8") (pin "82") (pinfunction "82_82") (pintype "passive"))
    )
    (net (code "331") (name "unconnected-(J8-Pad83)") (class "Default")
      (node (ref "J8") (pin "83") (pinfunction "83_83") (pintype "passive"))
    )
    (net (code "332") (name "unconnected-(J8-Pad84)") (class "Default")
      (node (ref "J8") (pin "84") (pinfunction "84_84") (pintype "passive"))
    )
    (net (code "333") (name "unconnected-(J8-Pad85)") (class "Default")
      (node (ref "J8") (pin "85") (pinfunction "85_85") (pintype "passive"))
    )
    (net (code "334") (name "unconnected-(J8-Pad86)") (class "Default")
      (node (ref "J8") (pin "86") (pinfunction "86_86") (pintype "passive"))
    )
    (net (code "335") (name "unconnected-(J8-Pad87)") (class "Default")
      (node (ref "J8") (pin "87") (pinfunction "87_87") (pintype "passive"))
    )
    (net (code "336") (name "unconnected-(J8-Pad88)") (class "Default")
      (node (ref "J8") (pin "88") (pinfunction "88_88") (pintype "passive"))
    )
    (net (code "337") (name "unconnected-(J8-Pad89)") (class "Default")
      (node (ref "J8") (pin "89") (pinfunction "89_89") (pintype "passive"))
    )
    (net (code "338") (name "unconnected-(J8-Pad90)") (class "Default")
      (node (ref "J8") (pin "90") (pinfunction "90_90") (pintype "passive"))
    )
    (net (code "339") (name "unconnected-(J8-Pad91)") (class "Default")
      (node (ref "J8") (pin "91") (pinfunction "91_91") (pintype "passive"))
    )
    (net (code "340") (name "unconnected-(J8-Pad92)") (class "Default")
      (node (ref "J8") (pin "92") (pinfunction "92_92") (pintype "passive"))
    )
    (net (code "341") (name "unconnected-(J8-Pad93)") (class "Default")
      (node (ref "J8") (pin "93") (pinfunction "93_93") (pintype "passive"))
    )
    (net (code "342") (name "unconnected-(J8-Pad94)") (class "Default")
      (node (ref "J8") (pin "94") (pinfunction "94_94") (pintype "passive"))
    )
    (net (code "343") (name "unconnected-(J8-Pad95)") (class "Default")
      (node (ref "J8") (pin "95") (pinfunction "95_95") (pintype "passive"))
    )
    (net (code "344") (name "unconnected-(J8-Pad96)") (class "Default")
      (node (ref "J8") (pin "96") (pinfunction "96_96") (pintype "passive"))
    )
    (net (code "345") (name "unconnected-(J8-Pad97)") (class "Default")
      (node (ref "J8") (pin "97") (pinfunction "97_97") (pintype "passive"))
    )
    (net (code "346") (name "unconnected-(J8-Pad98)") (class "Default")
      (node (ref "J8") (pin "98") (pinfunction "98_98") (pintype "passive"))
    )
    (net (code "347") (name "unconnected-(J8-Pad99)") (class "Default")
      (node (ref "J8") (pin "99") (pinfunction "99_99") (pintype "passive"))
    )
    (net (code "348") (name "unconnected-(J8-Pad100)") (class "Default")
      (node (ref "J8") (pin "100") (pinfunction "100_100") (pintype "passive"))
    )
    (net (code "349") (name "unconnected-(J8-Pad101)") (class "Default")
      (node (ref "J8") (pin "101") (pinfunction "101_101") (pintype "passive"))
    )
    (net (code "350") (name "unconnected-(J8-Pad102)") (class "Default")
      (node (ref "J8") (pin "102") (pinfunction "102_102") (pintype "passive"))
    )
    (net (code "351") (name "unconnected-(J8-Pad103)") (class "Default")
      (node (ref "J8") (pin "103") (pinfunction "103_103") (pintype "passive"))
    )
    (net (code "352") (name "unconnected-(J8-Pad104)") (class "Default")
      (node (ref "J8") (pin "104") (pinfunction "104_104") (pintype "passive"))
    )
  )
)
